# soc.net
KiCad netlist of a schematic drawn in Altium Designer
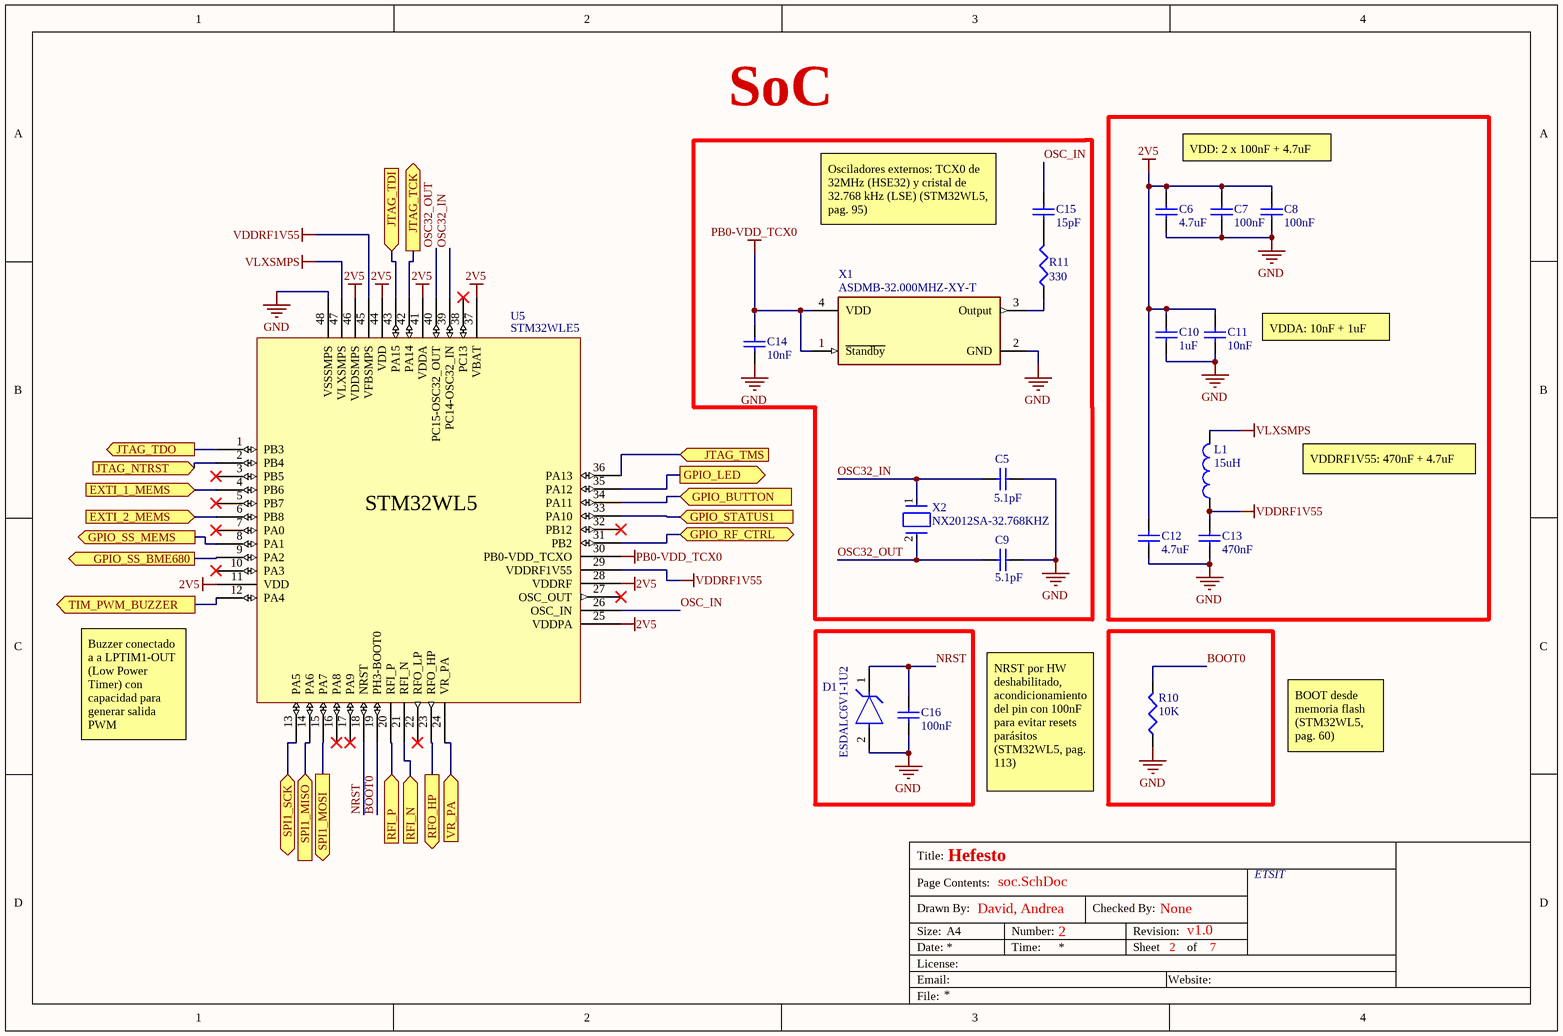
[diagram p0: soc.SchDoc]

(export (version "E")
  (design (tool "Eeschema 10.0.6"))
  (components
    (comp (ref "C5")
      (value "5.1pF")
      (footprint "1608[0603]")
      (description "Capacitor (Semiconductor SIM Model)")
      (fields (field (name "Comment") "Cap Semi") (field (name "PUBLISHER") "Altium Limited"))
      (libsource (lib "Miscellaneous Devices") (part "Cap Semi"))
    )
    (comp (ref "C6")
      (value "4.7uF")
      (footprint "1608[0603]")
      (description "Capacitor (Semiconductor SIM Model)")
      (fields (field (name "Comment") "Cap Semi") (field (name "PUBLISHER") "Altium Limited"))
      (libsource (lib "Miscellaneous Devices") (part "Cap Semi"))
    )
    (comp (ref "C7")
      (value "100nF")
      (footprint "1608[0603]")
      (description "Capacitor (Semiconductor SIM Model)")
      (fields (field (name "Comment") "Cap Semi") (field (name "PUBLISHER") "Altium Limited"))
      (libsource (lib "Miscellaneous Devices") (part "Cap Semi"))
    )
    (comp (ref "C8")
      (value "100nF")
      (footprint "1608[0603]")
      (description "Capacitor (Semiconductor SIM Model)")
      (fields (field (name "Comment") "Cap Semi") (field (name "PUBLISHER") "Altium Limited"))
      (libsource (lib "Miscellaneous Devices") (part "Cap Semi"))
    )
    (comp (ref "C9")
      (value "5.1pF")
      (footprint "1608[0603]")
      (description "Capacitor (Semiconductor SIM Model)")
      (fields (field (name "Comment") "Cap Semi") (field (name "PUBLISHER") "Altium Limited"))
      (libsource (lib "Miscellaneous Devices") (part "Cap Semi"))
    )
    (comp (ref "C10")
      (value "1uF")
      (footprint "1608[0603]")
      (description "Capacitor (Semiconductor SIM Model)")
      (fields (field (name "Comment") "Cap Semi") (field (name "PUBLISHER") "Altium Limited"))
      (libsource (lib "Miscellaneous Devices") (part "Cap Semi"))
    )
    (comp (ref "C11")
      (value "10nF")
      (footprint "1608[0603]")
      (description "Capacitor (Semiconductor SIM Model)")
      (fields (field (name "Comment") "Cap Semi") (field (name "PUBLISHER") "Altium Limited"))
      (libsource (lib "Miscellaneous Devices") (part "Cap Semi"))
    )
    (comp (ref "C12")
      (value "4.7uF")
      (footprint "1608[0603]")
      (description "Capacitor (Semiconductor SIM Model)")
      (fields (field (name "Comment") "Cap Semi") (field (name "PUBLISHER") "Altium Limited"))
      (libsource (lib "Miscellaneous Devices") (part "Cap Semi"))
    )
    (comp (ref "C13")
      (value "470nF")
      (footprint "1608[0603]")
      (description "Capacitor (Semiconductor SIM Model)")
      (fields (field (name "Comment") "Cap Semi") (field (name "PUBLISHER") "Altium Limited"))
      (libsource (lib "Miscellaneous Devices") (part "Cap Semi"))
    )
    (comp (ref "C14")
      (value "10nF")
      (footprint "1608[0603]")
      (description "Capacitor (Semiconductor SIM Model)")
      (fields (field (name "Comment") "Cap Semi") (field (name "PUBLISHER") "Altium Limited"))
      (libsource (lib "Miscellaneous Devices") (part "Cap Semi"))
    )
    (comp (ref "C15")
      (value "15pF")
      (footprint "1608[0603]")
      (description "Capacitor (Semiconductor SIM Model)")
      (fields (field (name "Comment") "Cap Semi") (field (name "PUBLISHER") "Altium Limited"))
      (libsource (lib "Miscellaneous Devices") (part "Cap Semi"))
    )
    (comp (ref "C16")
      (value "100nF")
      (footprint "1608[0603]")
      (description "Capacitor (Semiconductor SIM Model)")
      (fields (field (name "Comment") "Cap Semi") (field (name "PUBLISHER") "Altium Limited"))
      (libsource (lib "Miscellaneous Devices") (part "Cap Semi"))
    )
    (comp (ref "D1")
      (value "ESDALC6V1-1U2")
      (footprint "FP-ST0201-MFG")
      (description "TVS DIODE 3V ST0201")
      (fields
        (field (name "OCTOPART") "https://octopart.com/esdalc6v1-1u2-stmicroelectronics-11912330")
        (field (name "MANUFACTURER") "STMicroelectronics")
      )
      (libsource (lib "ESDALC6V1-1U2") (part "CMP-12225-000007-1"))
    )
    (comp (ref "L1")
      (value "15uH")
      (footprint "0603")
      (description "Inductor")
      (fields (field (name "PUBLISHER") "Altium Limited"))
      (libsource (lib "Miscellaneous Devices") (part "Inductor"))
    )
    (comp (ref "R10")
      (value "10K")
      (footprint "J1-0603")
      (description "Resistor")
      (fields (field (name "Comment") "Res3") (field (name "PUBLISHER") "Altium Limited"))
      (libsource (lib "Miscellaneous Devices") (part "Res3"))
    )
    (comp (ref "R11")
      (value "330")
      (footprint "J1-0603")
      (description "Resistor")
      (fields (field (name "Comment") "Res3") (field (name "PUBLISHER") "Altium Limited"))
      (libsource (lib "Miscellaneous Devices") (part "Res3"))
    )
    (comp (ref "U5")
      (value "STM32WLE5")
      (footprint "UFQFPN48")
      (libsource (lib "DEOP2023") (part "STM32WLE5"))
    )
    (comp (ref "X1")
      (value "ASDMB-32.000MHZ-XY-T")
      (footprint "FP-ASDM-ASDMB-MFG")
      (description "MEMS Oscillator 32MHz ±10ppm LVCMOS 1.8V~3.3V SMD 2.5x2mm")
      (libsource (lib "Osc 32mhz") (part "CMP-27762-009266-1"))
    )
    (comp (ref "X2")
      (value "NX2012SA-32.768KHZ")
      (footprint "FP-NX2012SA-MFG")
      (description "CRYSTAL 32.7680KHZ 6PF SMD")
      (libsource (lib "Altium Content Vault") (part "c23a69dc6c9e2f18f2079038eb95dd1"))
    )
  )
  (nets
    (net (code "1") (name "/BOOT0") (class "Default")
      (node (ref "R10") (pin "2") (pinfunction "2_2") (pintype "passive"))
      (node (ref "U5") (pin "19") (pinfunction "PH3-BOOT0_19") (pintype "bidirectional"))
    )
    (net (code "2") (name "/EXTI_1_MEMS") (class "Default")
      (node (ref "U5") (pin "4") (pinfunction "PB6_4") (pintype "bidirectional"))
    )
    (net (code "3") (name "/EXTI_2_MEMS") (class "Default")
      (node (ref "U5") (pin "6") (pinfunction "PB8_6") (pintype "bidirectional"))
    )
    (net (code "4") (name "/GPIO_BUTTON") (class "Default")
      (node (ref "U5") (pin "34") (pinfunction "PA11_34") (pintype "bidirectional"))
    )
    (net (code "5") (name "/GPIO_LED") (class "Default")
      (node (ref "U5") (pin "35") (pinfunction "PA12_35") (pintype "bidirectional"))
    )
    (net (code "6") (name "/GPIO_RF_CTRL") (class "Default")
      (node (ref "U5") (pin "31") (pinfunction "PB2_31") (pintype "bidirectional"))
    )
    (net (code "7") (name "/GPIO_SS_BME680") (class "Default")
      (node (ref "U5") (pin "9") (pinfunction "PA2_9") (pintype "bidirectional"))
    )
    (net (code "8") (name "/GPIO_SS_MEMS") (class "Default")
      (node (ref "U5") (pin "8") (pinfunction "PA1_8") (pintype "bidirectional"))
    )
    (net (code "9") (name "/GPIO_STATUS1") (class "Default")
      (node (ref "U5") (pin "33") (pinfunction "PA10_33") (pintype "bidirectional"))
    )
    (net (code "10") (name "/JTAG_NTRST") (class "Default")
      (node (ref "U5") (pin "2") (pinfunction "PB4_2") (pintype "bidirectional"))
    )
    (net (code "11") (name "/JTAG_TCK") (class "Default")
      (node (ref "U5") (pin "42") (pinfunction "PA14_42") (pintype "bidirectional"))
    )
    (net (code "12") (name "/JTAG_TDI") (class "Default")
      (node (ref "U5") (pin "43") (pinfunction "PA15_43") (pintype "bidirectional"))
    )
    (net (code "13") (name "/JTAG_TDO") (class "Default")
      (node (ref "U5") (pin "1") (pinfunction "PB3_1") (pintype "bidirectional"))
    )
    (net (code "14") (name "/JTAG_TMS") (class "Default")
      (node (ref "U5") (pin "36") (pinfunction "PA13_36") (pintype "bidirectional"))
    )
    (net (code "15") (name "/NRST") (class "Default")
      (node (ref "C16") (pin "2") (pinfunction "2_2") (pintype "passive"))
      (node (ref "D1") (pin "1") (pinfunction "C_1") (pintype "passive"))
      (node (ref "U5") (pin "18") (pinfunction "NRST_18") (pintype "bidirectional"))
    )
    (net (code "16") (name "/OSC32_IN") (class "Default")
      (node (ref "C5") (pin "2") (pinfunction "2_2") (pintype "passive"))
      (node (ref "U5") (pin "39") (pinfunction "PC14-OSC32_IN_39") (pintype "bidirectional"))
      (node (ref "X2") (pin "1") (pinfunction "1_1") (pintype "passive"))
    )
    (net (code "17") (name "/OSC32_OUT") (class "Default")
      (node (ref "C9") (pin "2") (pinfunction "2_2") (pintype "passive"))
      (node (ref "U5") (pin "40") (pinfunction "PC15-OSC32_OUT_40") (pintype "bidirectional"))
      (node (ref "X2") (pin "2") (pinfunction "2_2") (pintype "passive"))
    )
    (net (code "18") (name "/OSC_IN") (class "Default")
      (node (ref "C15") (pin "2") (pinfunction "2_2") (pintype "passive"))
      (node (ref "U5") (pin "26") (pinfunction "OSC_IN_26") (pintype "passive"))
    )
    (net (code "19") (name "/RFI_N") (class "Default")
      (node (ref "U5") (pin "21") (pinfunction "RFI_N_21") (pintype "passive"))
    )
    (net (code "20") (name "/RFI_P") (class "Default")
      (node (ref "U5") (pin "20") (pinfunction "RFI_P_20") (pintype "passive"))
    )
    (net (code "21") (name "/RFO_HP") (class "Default")
      (node (ref "U5") (pin "23") (pinfunction "RFO_HP_23") (pintype "output"))
    )
    (net (code "22") (name "/SPI1_MISO") (class "Default")
      (node (ref "U5") (pin "14") (pinfunction "PA6_14") (pintype "bidirectional"))
    )
    (net (code "23") (name "/SPI1_MOSI") (class "Default")
      (node (ref "U5") (pin "15") (pinfunction "PA7_15") (pintype "bidirectional"))
    )
    (net (code "24") (name "/SPI1_SCK") (class "Default")
      (node (ref "U5") (pin "13") (pinfunction "PA5_13") (pintype "bidirectional"))
    )
    (net (code "25") (name "/TIM_PWM_BUZZER") (class "Default")
      (node (ref "U5") (pin "12") (pinfunction "PA4_12") (pintype "bidirectional"))
    )
    (net (code "26") (name "/VR_PA") (class "Default")
      (node (ref "U5") (pin "24") (pinfunction "VR_PA_24") (pintype "passive"))
    )
    (net (code "27") (name "2V5") (class "Default")
      (node (ref "C10") (pin "2") (pinfunction "2_2") (pintype "passive"))
      (node (ref "C11") (pin "2") (pinfunction "2_2") (pintype "passive"))
      (node (ref "C12") (pin "2") (pinfunction "2_2") (pintype "passive"))
      (node (ref "C6") (pin "2") (pinfunction "2_2") (pintype "passive"))
      (node (ref "C7") (pin "2") (pinfunction "2_2") (pintype "passive"))
      (node (ref "C8") (pin "2") (pinfunction "2_2") (pintype "passive"))
      (node (ref "U5") (pin "11") (pinfunction "VDD_11") (pintype "power_in"))
      (node (ref "U5") (pin "25") (pinfunction "VDDPA_25") (pintype "power_in"))
      (node (ref "U5") (pin "28") (pinfunction "VDDRF_28") (pintype "power_in"))
      (node (ref "U5") (pin "37") (pinfunction "VBAT_37") (pintype "power_in"))
      (node (ref "U5") (pin "41") (pinfunction "VDDA_41") (pintype "power_in"))
      (node (ref "U5") (pin "44") (pinfunction "VDD_44") (pintype "power_in"))
      (node (ref "U5") (pin "46") (pinfunction "VDDSMPS_46") (pintype "power_in"))
    )
    (net (code "28") (name "GND") (class "Default")
      (node (ref "C10") (pin "1") (pinfunction "1_1") (pintype "passive"))
      (node (ref "C11") (pin "1") (pinfunction "1_1") (pintype "passive"))
      (node (ref "C12") (pin "1") (pinfunction "1_1") (pintype "passive"))
      (node (ref "C13") (pin "1") (pinfunction "1_1") (pintype "passive"))
      (node (ref "C14") (pin "1") (pinfunction "1_1") (pintype "passive"))
      (node (ref "C16") (pin "1") (pinfunction "1_1") (pintype "passive"))
      (node (ref "C5") (pin "1") (pinfunction "1_1") (pintype "passive"))
      (node (ref "C6") (pin "1") (pinfunction "1_1") (pintype "passive"))
      (node (ref "C7") (pin "1") (pinfunction "1_1") (pintype "passive"))
      (node (ref "C8") (pin "1") (pinfunction "1_1") (pintype "passive"))
      (node (ref "C9") (pin "1") (pinfunction "1_1") (pintype "passive"))
      (node (ref "D1") (pin "2") (pinfunction "A_2") (pintype "passive"))
      (node (ref "R10") (pin "1") (pinfunction "1_1") (pintype "passive"))
      (node (ref "U5") (pin "48") (pinfunction "VSSSMPS_48") (pintype "power_in"))
      (node (ref "X1") (pin "2") (pinfunction "GND_2") (pintype "power_in"))
    )
    (net (code "29") (name "Net-(C15-Pad1)") (class "Default")
      (node (ref "C15") (pin "1") (pinfunction "1_1") (pintype "passive"))
      (node (ref "R11") (pin "2") (pinfunction "2_2") (pintype "passive"))
    )
    (net (code "30") (name "Net-(X1-Output)") (class "Default")
      (node (ref "R11") (pin "1") (pinfunction "1_1") (pintype "passive"))
      (node (ref "X1") (pin "3") (pinfunction "Output_3") (pintype "output"))
    )
    (net (code "31") (name "PB0-VDD_TCX0") (class "Default")
      (node (ref "C14") (pin "2") (pinfunction "2_2") (pintype "passive"))
      (node (ref "U5") (pin "30") (pinfunction "PB0-VDD_TCXO_30") (pintype "power_in"))
      (node (ref "X1") (pin "1") (pinfunction "~{Standby}_1") (pintype "input"))
      (node (ref "X1") (pin "4") (pinfunction "VDD_4") (pintype "power_in"))
    )
    (net (code "32") (name "VDDRF1V55") (class "Default")
      (node (ref "C13") (pin "2") (pinfunction "2_2") (pintype "passive"))
      (node (ref "L1") (pin "1") (pinfunction "1_1") (pintype "passive"))
      (node (ref "U5") (pin "29") (pinfunction "VDDRF1V55_29") (pintype "power_in"))
      (node (ref "U5") (pin "45") (pinfunction "VFBSMPS_45") (pintype "power_in"))
    )
    (net (code "33") (name "VLXSMPS") (class "Default")
      (node (ref "L1") (pin "2") (pinfunction "2_2") (pintype "passive"))
      (node (ref "U5") (pin "47") (pinfunction "VLXSMPS_47") (pintype "power_in"))
    )
    (net (code "34") (name "unconnected-(U5-OSC_OUT-Pad27)") (class "Default")
      (node (ref "U5") (pin "27") (pinfunction "OSC_OUT_27") (pintype "output+no_connect"))
    )
    (net (code "35") (name "unconnected-(U5-PA0-Pad7)") (class "Default")
      (node (ref "U5") (pin "7") (pinfunction "PA0_7") (pintype "bidirectional+no_connect"))
    )
    (net (code "36") (name "unconnected-(U5-PA3-Pad10)") (class "Default")
      (node (ref "U5") (pin "10") (pinfunction "PA3_10") (pintype "bidirectional+no_connect"))
    )
    (net (code "37") (name "unconnected-(U5-PA8-Pad16)") (class "Default")
      (node (ref "U5") (pin "16") (pinfunction "PA8_16") (pintype "bidirectional+no_connect"))
    )
    (net (code "38") (name "unconnected-(U5-PA9-Pad17)") (class "Default")
      (node (ref "U5") (pin "17") (pinfunction "PA9_17") (pintype "bidirectional+no_connect"))
    )
    (net (code "39") (name "unconnected-(U5-PB5-Pad3)") (class "Default")
      (node (ref "U5") (pin "3") (pinfunction "PB5_3") (pintype "bidirectional+no_connect"))
    )
    (net (code "40") (name "unconnected-(U5-PB7-Pad5)") (class "Default")
      (node (ref "U5") (pin "5") (pinfunction "PB7_5") (pintype "bidirectional+no_connect"))
    )
    (net (code "41") (name "unconnected-(U5-PB12-Pad32)") (class "Default")
      (node (ref "U5") (pin "32") (pinfunction "PB12_32") (pintype "bidirectional+no_connect"))
    )
    (net (code "42") (name "unconnected-(U5-PC13-Pad38)") (class "Default")
      (node (ref "U5") (pin "38") (pinfunction "PC13_38") (pintype "bidirectional+no_connect"))
    )
    (net (code "43") (name "unconnected-(U5-RFO_LP-Pad22)") (class "Default")
      (node (ref "U5") (pin "22") (pinfunction "RFO_LP_22") (pintype "output+no_connect"))
    )
  )
)
